# sc16is752.net
KiCad netlist of a schematic drawn in Altium Designer
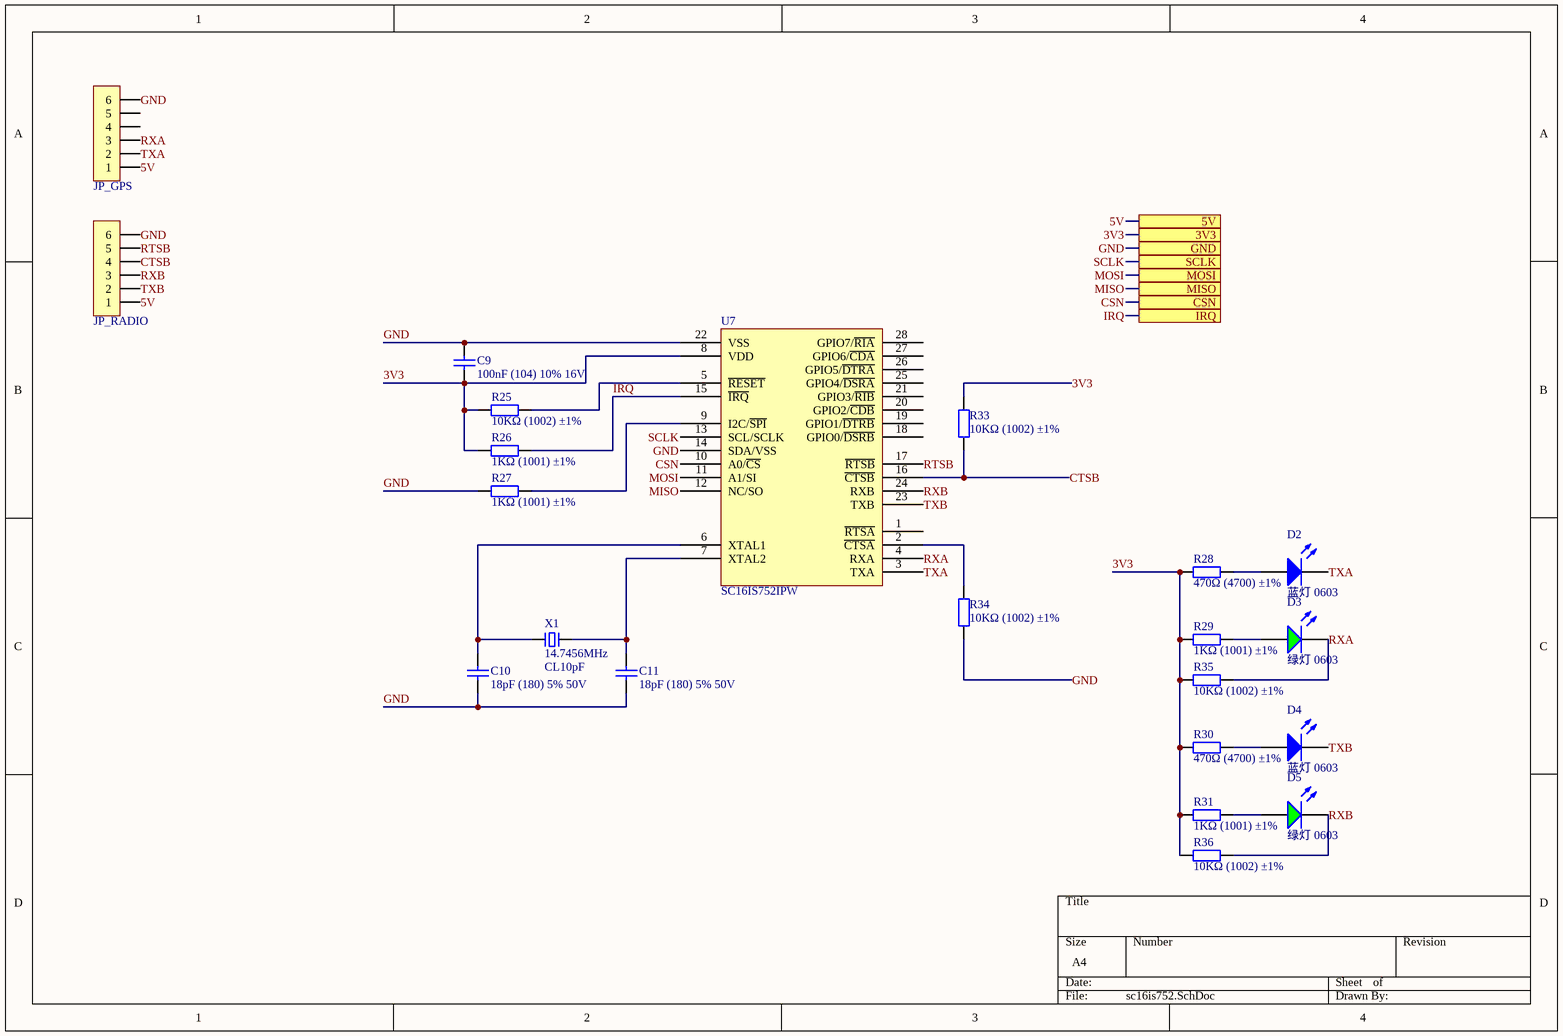
[diagram p0: sc16is752.SchDoc]

(export (version "E")
  (design (tool "Eeschema 10.0.6"))
  (components
    (comp (ref "C9")
      (value "100nF (104) 10% 16V")
      (footprint "0402_C")
      (description "贴片电容")
      (libsource (lib "Miscellaneous Devices LC") (part "0402 100nF (104) 10% 16V"))
    )
    (comp (ref "C10")
      (value "18pF (180) 5% 50V")
      (footprint "0402_C")
      (description "贴片电容")
      (libsource (lib "Miscellaneous Devices LC") (part "0402 18pF (180) 5% 50V"))
    )
    (comp (ref "C11")
      (value "18pF (180) 5% 50V")
      (footprint "0402_C")
      (description "贴片电容")
      (libsource (lib "Miscellaneous Devices LC") (part "0402 18pF (180) 5% 50V"))
    )
    (comp (ref "D2")
      (value "蓝灯 0603")
      (footprint "0603_LED_S1")
      (description "发光二极管")
      (libsource (lib "Miscellaneous Devices LC") (part "0603 蓝灯"))
    )
    (comp (ref "D3")
      (value "绿灯 0603")
      (footprint "0603_LED_S1")
      (description "发光二极管")
      (libsource (lib "Miscellaneous Devices LC") (part "0603 绿灯"))
    )
    (comp (ref "D4")
      (value "蓝灯 0603")
      (footprint "0603_LED_S1")
      (description "发光二极管")
      (libsource (lib "Miscellaneous Devices LC") (part "0603 蓝灯"))
    )
    (comp (ref "D5")
      (value "绿灯 0603")
      (footprint "0603_LED_S1")
      (description "发光二极管")
      (libsource (lib "Miscellaneous Devices LC") (part "0603 绿灯"))
    )
    (comp (ref "JP_GPS")
      (value "HDR-1X6")
      (footprint "MX 1.25-WS-6P")
      (description "6P接插件")
      (fields (field (name "版权归属") "源创客"))
      (libsource (lib "4.2   - 接插件-脚距1.25") (part "Header 6"))
    )
    (comp (ref "JP_RADIO")
      (value "HDR-1X6")
      (footprint "MX 1.25-WS-6P")
      (description "6P接插件")
      (fields (field (name "版权归属") "源创客"))
      (libsource (lib "4.2   - 接插件-脚距1.25") (part "Header 6"))
    )
    (comp (ref "R25")
      (value "10KΩ (1002) ±1%")
      (footprint "0402_R")
      (description "贴片电阻")
      (libsource (lib "") (part "0402 10KΩ (1002) 1%_1"))
    )
    (comp (ref "R26")
      (value "1KΩ (1001) ±1%")
      (footprint "0402_R")
      (description "贴片电阻")
      (libsource (lib "Miscellaneous Devices LC") (part "0402 1KΩ (1001) 1%"))
    )
    (comp (ref "R27")
      (value "1KΩ (1001) ±1%")
      (footprint "0402_R")
      (description "贴片电阻")
      (libsource (lib "Miscellaneous Devices LC") (part "0402 1KΩ (1001) 1%"))
    )
    (comp (ref "R28")
      (value "470Ω (4700) ±1%")
      (footprint "0402_R")
      (description "贴片电阻")
      (libsource (lib "Miscellaneous Devices LC") (part "0402 470Ω (4700) 1%"))
    )
    (comp (ref "R29")
      (value "1KΩ (1001) ±1%")
      (footprint "0402_R")
      (description "贴片电阻")
      (libsource (lib "Miscellaneous Devices LC") (part "0402 1KΩ (1001) 1%"))
    )
    (comp (ref "R30")
      (value "470Ω (4700) ±1%")
      (footprint "0402_R")
      (description "贴片电阻")
      (libsource (lib "Miscellaneous Devices LC") (part "0402 470Ω (4700) 1%"))
    )
    (comp (ref "R31")
      (value "1KΩ (1001) ±1%")
      (footprint "0402_R")
      (description "贴片电阻")
      (libsource (lib "Miscellaneous Devices LC") (part "0402 1KΩ (1001) 1%"))
    )
    (comp (ref "R33")
      (value "10KΩ (1002) ±1%")
      (footprint "0402_R")
      (description "贴片电阻")
      (libsource (lib "Miscellaneous Devices LC") (part "0402 10KΩ (1002) 1%"))
    )
    (comp (ref "R34")
      (value "10KΩ (1002) ±1%")
      (footprint "0402_R")
      (description "贴片电阻")
      (libsource (lib "Miscellaneous Devices LC") (part "0402 10KΩ (1002) 1%"))
    )
    (comp (ref "R35")
      (value "10KΩ (1002) ±1%")
      (footprint "0402_R")
      (description "贴片电阻")
      (libsource (lib "") (part "0402 10KΩ (1002) 1%_2"))
    )
    (comp (ref "R36")
      (value "10KΩ (1002) ±1%")
      (footprint "0402_R")
      (description "贴片电阻")
      (libsource (lib "") (part "0402 10KΩ (1002) 1%_2"))
    )
    (comp (ref "U7")
      (value "SC16IS752IPW")
      (footprint "TSSOP28_n")
      (libsource (lib "SC16IS752_SC16IS762") (part "SC16IS752IPW"))
    )
    (comp (ref "X1")
      (value "14.7456MHz")
      (footprint "OSC HC-49SMD")
      (description "2脚无源脚晶振")
      (fields (field (name "负载电容") "CL10pF") (field (name "版权归属") "源创客"))
      (libsource (lib "10.1 - 保险丝-晶振") (part "XTAL-2P"))
    )
  )
  (nets
    (net (code "1") (name "/3V3") (class "Default")
      (node (ref "C9") (pin "1") (pinfunction "1_1") (pintype "passive"))
      (node (ref "R25") (pin "1") (pinfunction "1_1") (pintype "passive"))
      (node (ref "R26") (pin "1") (pinfunction "1_1") (pintype "passive"))
      (node (ref "R28") (pin "1") (pinfunction "1_1") (pintype "passive"))
      (node (ref "R29") (pin "1") (pinfunction "1_1") (pintype "passive"))
      (node (ref "R30") (pin "1") (pinfunction "1_1") (pintype "passive"))
      (node (ref "R31") (pin "1") (pinfunction "1_1") (pintype "passive"))
      (node (ref "R33") (pin "2") (pinfunction "2_2") (pintype "passive"))
      (node (ref "R35") (pin "2") (pinfunction "2_2") (pintype "passive"))
      (node (ref "R36") (pin "2") (pinfunction "2_2") (pintype "passive"))
      (node (ref "U7") (pin "8") (pinfunction "VDD_8") (pintype "passive"))
    )
    (net (code "2") (name "/5V") (class "Default")
      (node (ref "JP_GPS") (pin "1") (pinfunction "1_1") (pintype "passive"))
      (node (ref "JP_RADIO") (pin "1") (pinfunction "1_1") (pintype "passive"))
    )
    (net (code "3") (name "/CSN") (class "Default")
      (node (ref "U7") (pin "10") (pinfunction "A0/~{CS}_10") (pintype "passive"))
    )
    (net (code "4") (name "/CTSB") (class "Default")
      (node (ref "JP_RADIO") (pin "4") (pinfunction "4_4") (pintype "passive"))
      (node (ref "R33") (pin "1") (pinfunction "1_1") (pintype "passive"))
      (node (ref "U7") (pin "16") (pinfunction "~{CTSB}_16") (pintype "passive"))
    )
    (net (code "5") (name "/GND") (class "Default")
      (node (ref "C10") (pin "1") (pinfunction "1_1") (pintype "passive"))
      (node (ref "C11") (pin "1") (pinfunction "1_1") (pintype "passive"))
      (node (ref "C9") (pin "2") (pinfunction "2_2") (pintype "passive"))
      (node (ref "JP_GPS") (pin "6") (pinfunction "6_6") (pintype "passive"))
      (node (ref "JP_RADIO") (pin "6") (pinfunction "6_6") (pintype "passive"))
      (node (ref "R27") (pin "1") (pinfunction "1_1") (pintype "passive"))
      (node (ref "R34") (pin "1") (pinfunction "1_1") (pintype "passive"))
      (node (ref "U7") (pin "14") (pinfunction "SDA/VSS_14") (pintype "passive"))
      (node (ref "U7") (pin "22") (pinfunction "VSS_22") (pintype "passive"))
    )
    (net (code "6") (name "/IRQ") (class "Default")
      (node (ref "R26") (pin "2") (pinfunction "2_2") (pintype "passive"))
      (node (ref "U7") (pin "15") (pinfunction "~{IRQ}_15") (pintype "passive"))
    )
    (net (code "7") (name "/MISO") (class "Default")
      (node (ref "U7") (pin "12") (pinfunction "NC/SO_12") (pintype "passive"))
    )
    (net (code "8") (name "/MOSI") (class "Default")
      (node (ref "U7") (pin "11") (pinfunction "A1/SI_11") (pintype "passive"))
    )
    (net (code "9") (name "/RTSB") (class "Default")
      (node (ref "JP_RADIO") (pin "5") (pinfunction "5_5") (pintype "passive"))
      (node (ref "U7") (pin "17") (pinfunction "~{RTSB}_17") (pintype "passive"))
    )
    (net (code "10") (name "/RXA") (class "Default")
      (node (ref "D3") (pin "K") (pinfunction "K_K") (pintype "passive"))
      (node (ref "JP_GPS") (pin "3") (pinfunction "3_3") (pintype "passive"))
      (node (ref "R35") (pin "1") (pinfunction "1_1") (pintype "passive"))
      (node (ref "U7") (pin "4") (pinfunction "RXA_4") (pintype "passive"))
    )
    (net (code "11") (name "/RXB") (class "Default")
      (node (ref "D5") (pin "K") (pinfunction "K_K") (pintype "passive"))
      (node (ref "JP_RADIO") (pin "3") (pinfunction "3_3") (pintype "passive"))
      (node (ref "R36") (pin "1") (pinfunction "1_1") (pintype "passive"))
      (node (ref "U7") (pin "24") (pinfunction "RXB_24") (pintype "passive"))
    )
    (net (code "12") (name "/SCLK") (class "Default")
      (node (ref "U7") (pin "13") (pinfunction "SCL/SCLK_13") (pintype "passive"))
    )
    (net (code "13") (name "/TXA") (class "Default")
      (node (ref "D2") (pin "K") (pinfunction "K_K") (pintype "passive"))
      (node (ref "JP_GPS") (pin "2") (pinfunction "2_2") (pintype "passive"))
      (node (ref "U7") (pin "3") (pinfunction "TXA_3") (pintype "passive"))
    )
    (net (code "14") (name "/TXB") (class "Default")
      (node (ref "D4") (pin "K") (pinfunction "K_K") (pintype "passive"))
      (node (ref "JP_RADIO") (pin "2") (pinfunction "2_2") (pintype "passive"))
      (node (ref "U7") (pin "23") (pinfunction "TXB_23") (pintype "passive"))
    )
    (net (code "15") (name "Net-(D2-PadA)") (class "Default")
      (node (ref "D2") (pin "A") (pinfunction "A_A") (pintype "passive"))
      (node (ref "R28") (pin "2") (pinfunction "2_2") (pintype "passive"))
    )
    (net (code "16") (name "Net-(D3-PadA)") (class "Default")
      (node (ref "D3") (pin "A") (pinfunction "A_A") (pintype "passive"))
      (node (ref "R29") (pin "2") (pinfunction "2_2") (pintype "passive"))
    )
    (net (code "17") (name "Net-(D4-PadA)") (class "Default")
      (node (ref "D4") (pin "A") (pinfunction "A_A") (pintype "passive"))
      (node (ref "R30") (pin "2") (pinfunction "2_2") (pintype "passive"))
    )
    (net (code "18") (name "Net-(D5-PadA)") (class "Default")
      (node (ref "D5") (pin "A") (pinfunction "A_A") (pintype "passive"))
      (node (ref "R31") (pin "2") (pinfunction "2_2") (pintype "passive"))
    )
    (net (code "19") (name "Net-(U7-I2C{slash}~{SPI})") (class "Default")
      (node (ref "R27") (pin "2") (pinfunction "2_2") (pintype "passive"))
      (node (ref "U7") (pin "9") (pinfunction "I2C/~{SPI}_9") (pintype "passive"))
    )
    (net (code "20") (name "Net-(U7-XTAL1)") (class "Default")
      (node (ref "C10") (pin "2") (pinfunction "2_2") (pintype "passive"))
      (node (ref "U7") (pin "6") (pinfunction "XTAL1_6") (pintype "passive"))
      (node (ref "X1") (pin "1") (pinfunction "1_1") (pintype "passive"))
    )
    (net (code "21") (name "Net-(U7-XTAL2)") (class "Default")
      (node (ref "C11") (pin "2") (pinfunction "2_2") (pintype "passive"))
      (node (ref "U7") (pin "7") (pinfunction "XTAL2_7") (pintype "passive"))
      (node (ref "X1") (pin "2") (pinfunction "2_2") (pintype "passive"))
    )
    (net (code "22") (name "Net-(U7-~{CTSA})") (class "Default")
      (node (ref "R34") (pin "2") (pinfunction "2_2") (pintype "passive"))
      (node (ref "U7") (pin "2") (pinfunction "~{CTSA}_2") (pintype "passive"))
    )
    (net (code "23") (name "Net-(U7-~{RESET})") (class "Default")
      (node (ref "R25") (pin "2") (pinfunction "2_2") (pintype "passive"))
      (node (ref "U7") (pin "5") (pinfunction "~{RESET}_5") (pintype "passive"))
    )
    (net (code "24") (name "unconnected-(JP_GPS-Pad4)") (class "Default")
      (node (ref "JP_GPS") (pin "4") (pinfunction "4_4") (pintype "passive"))
    )
    (net (code "25") (name "unconnected-(JP_GPS-Pad5)") (class "Default")
      (node (ref "JP_GPS") (pin "5") (pinfunction "5_5") (pintype "passive"))
    )
    (net (code "26") (name "unconnected-(U7-GPIO0{slash}~{DSRB}-Pad18)") (class "Default")
      (node (ref "U7") (pin "18") (pinfunction "GPIO0/~{DSRB}_18") (pintype "passive"))
    )
    (net (code "27") (name "unconnected-(U7-GPIO1{slash}~{DTRB}-Pad19)") (class "Default")
      (node (ref "U7") (pin "19") (pinfunction "GPIO1/~{DTRB}_19") (pintype "passive"))
    )
    (net (code "28") (name "unconnected-(U7-GPIO2{slash}~{CDB}-Pad20)") (class "Default")
      (node (ref "U7") (pin "20") (pinfunction "GPIO2/~{CDB}_20") (pintype "passive"))
    )
    (net (code "29") (name "unconnected-(U7-GPIO3{slash}~{RIB}-Pad21)") (class "Default")
      (node (ref "U7") (pin "21") (pinfunction "GPIO3/~{RIB}_21") (pintype "passive"))
    )
    (net (code "30") (name "unconnected-(U7-GPIO4{slash}~{DSRA}-Pad25)") (class "Default")
      (node (ref "U7") (pin "25") (pinfunction "GPIO4/~{DSRA}_25") (pintype "passive"))
    )
    (net (code "31") (name "unconnected-(U7-GPIO5{slash}~{DTRA}-Pad26)") (class "Default")
      (node (ref "U7") (pin "26") (pinfunction "GPIO5/~{DTRA}_26") (pintype "passive"))
    )
    (net (code "32") (name "unconnected-(U7-GPIO6{slash}~{CDA}-Pad27)") (class "Default")
      (node (ref "U7") (pin "27") (pinfunction "GPIO6/~{CDA}_27") (pintype "passive"))
    )
    (net (code "33") (name "unconnected-(U7-GPIO7{slash}~{RIA}-Pad28)") (class "Default")
      (node (ref "U7") (pin "28") (pinfunction "GPIO7/~{RIA}_28") (pintype "passive"))
    )
    (net (code "34") (name "unconnected-(U7-~{RTSA}-Pad1)") (class "Default")
      (node (ref "U7") (pin "1") (pinfunction "~{RTSA}_1") (pintype "passive"))
    )
  )
)
